# adc_signal.net
KiCad netlist of a schematic drawn in Altium Designer
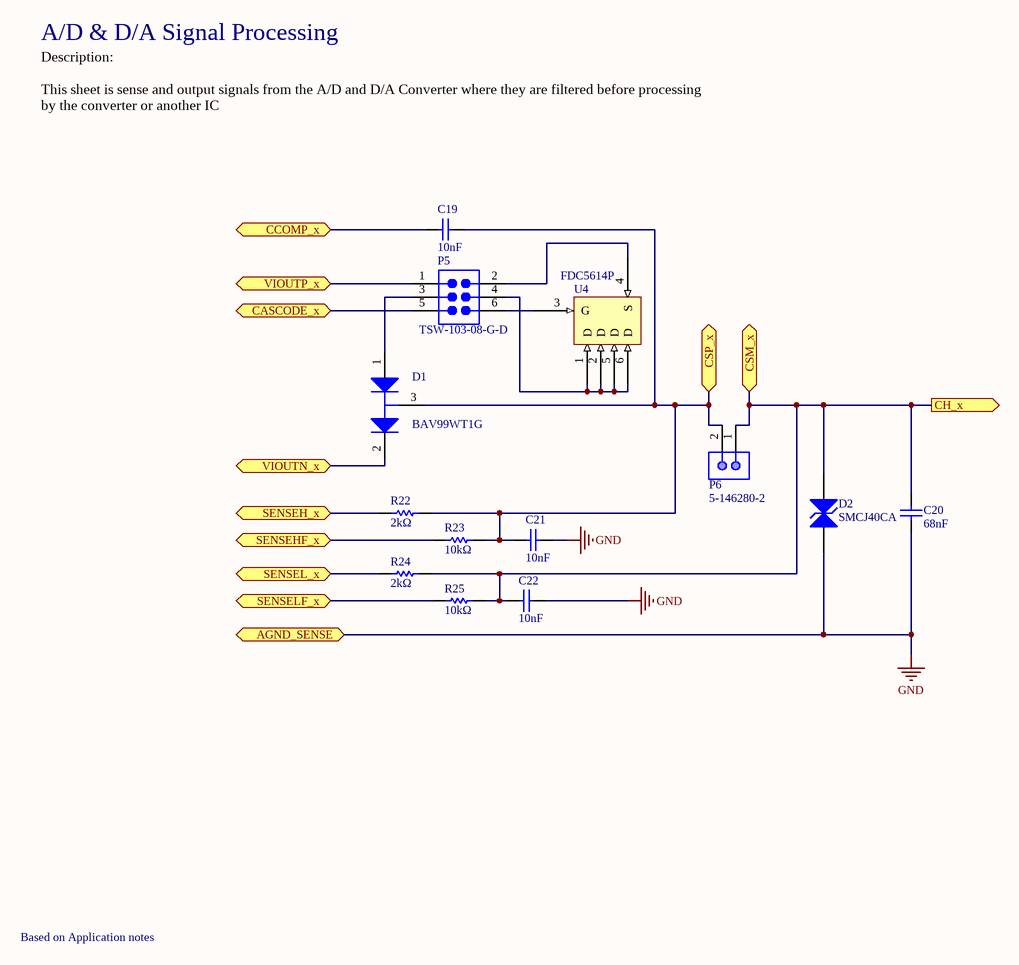
[diagram p0: adc_signal.SchDoc]

(export (version "E")
  (design (tool "Eeschema 10.0.6"))
  (components
    (comp (ref "C19")
      (value "10nF")
      (footprint "CAPC1608X90X35ML10T15")
      (fields
        (field (name "VOLTAGE") "50V")
        (field (name "TOLERANCE") "10%")
        (field (name "MANUFACTURER") "Murata")
      )
      (libsource (lib "Altium Content Vault") (part "CAP-NP-2"))
    )
    (comp (ref "C20")
      (value "68nF")
      (footprint "CAPC1608X90X35LL10T15")
      (description "GRM188R71H683KA93D")
      (fields (field (name "MANUFACTURER") "Murata"))
      (libsource (lib "Altium Content Vault") (part "CAP"))
    )
    (comp (ref "C21")
      (value "10nF")
      (footprint "CAPC1608X90X35ML10T15")
      (fields
        (field (name "VOLTAGE") "50V")
        (field (name "TOLERANCE") "10%")
        (field (name "MANUFACTURER") "Murata")
      )
      (libsource (lib "Altium Content Vault") (part "CAP-NP-2"))
    )
    (comp (ref "C22")
      (value "10nF")
      (footprint "CAPC1608X90X35ML10T15")
      (fields
        (field (name "VOLTAGE") "50V")
        (field (name "TOLERANCE") "10%")
        (field (name "MANUFACTURER") "Murata")
      )
      (libsource (lib "Altium Content Vault") (part "CAP-NP-2"))
    )
    (comp (ref "D1")
      (value "BAV99WT1G")
      (footprint "ONSC-SOT-323-3-419-04_V")
      (description "Dual Series Switching Diodes, 3-Pin SOT-323, Pb-Free, Tape and Reel")
      (fields (field (name "MANUFACTURER") "On Semiconductor"))
      (libsource (lib "Altium Content Vault") (part "ONSC-D-A1K2C3-3"))
    )
    (comp (ref "D2")
      (value "SMCJ40CA")
      (footprint "FAIR-DO-214AB-A-2_V")
      (description "Transient Voltage Suppressor, 1500 W, 40 V, 2-Pin SMD, RoHS, Tape and Reel")
      (fields (field (name "MANUFACTURER") "Fairchild Semiconductor"))
      (libsource (lib "Altium Content Vault") (part "DZEN-AA-2"))
    )
    (comp (ref "P5")
      (value "TSW-103-08-G-D")
      (footprint "SMTC-TSW-103-08-X-D")
      (description "0.025\" SQ Post Header, Through-hole, Vertical, -55 to 125 degC, 2.54 mm Pitch, 6-Pin, Male, RoHS")
      (fields (field (name "MANUFACTURER") "Samtec"))
      (libsource (lib "Altium Content Vault") (part "SMTC-TSW-103-08-X-D"))
    )
    (comp (ref "P6")
      (value "5-146280-2")
      (footprint "TECO-5-146280-2_V")
      (fields (field (name "MANUFACTURER") "TE Connectivity"))
      (libsource (lib "Altium Content Vault") (part "CN-1P-M-R2"))
    )
    (comp (ref "R22")
      (value "2kΩ")
      (footprint "RESC1608X55X30NL20T20")
      (description "ERA3AEB202V")
      (fields (field (name "MANUFACTURER") "Panasonic"))
      (libsource (lib "Altium Content Vault") (part "RES"))
    )
    (comp (ref "R23")
      (value "10kΩ")
      (footprint "RESC1608X55X25ML10T15")
      (fields (field (name "MANUFACTURER") "Yageo") (field (name "TOLERANCE") "1%"))
      (libsource (lib "Altium Content Vault") (part "RES-2"))
    )
    (comp (ref "R24")
      (value "2kΩ")
      (footprint "RESC1608X55X30NL20T20")
      (description "ERA3AEB202V")
      (fields (field (name "MANUFACTURER") "Panasonic"))
      (libsource (lib "Altium Content Vault") (part "RES"))
    )
    (comp (ref "R25")
      (value "10kΩ")
      (footprint "RESC1608X55X25ML10T15")
      (fields (field (name "MANUFACTURER") "Yageo") (field (name "TOLERANCE") "1%"))
      (libsource (lib "Altium Content Vault") (part "RES-2"))
    )
    (comp (ref "U4")
      (value "FDC5614P")
      (footprint "ONSC-CPH-6_V")
      (description "MOSFET P-CH 60V 3A SSOT-6")
      (fields (field (name "VOLTAGE") "60V"))
      (libsource (lib "digital_power") (part "FDC5614P"))
    )
  )
  (nets
    (net (code "1") (name "/CASCODE_x") (class "Default")
      (node (ref "P5") (pin "5") (pinfunction "5_5") (pintype "passive"))
    )
    (net (code "2") (name "/CCOMP_x") (class "Default")
      (node (ref "C19") (pin "1") (pinfunction "1_1") (pintype "passive"))
    )
    (net (code "3") (name "/CH_x") (class "Default")
      (node (ref "C20") (pin "2") (pinfunction "2_2") (pintype "passive"))
      (node (ref "C22") (pin "2") (pinfunction "2_2") (pintype "passive"))
      (node (ref "D2") (pin "2") (pinfunction "A_2") (pintype "passive"))
      (node (ref "P6") (pin "1") (pinfunction "1_1") (pintype "passive"))
      (node (ref "R24") (pin "2") (pinfunction "2_2") (pintype "passive"))
      (node (ref "R25") (pin "2") (pinfunction "2_2") (pintype "passive"))
    )
    (net (code "4") (name "/CSP_x") (class "Default")
      (node (ref "C19") (pin "2") (pinfunction "2_2") (pintype "passive"))
      (node (ref "C21") (pin "2") (pinfunction "2_2") (pintype "passive"))
      (node (ref "D1") (pin "3") (pinfunction "K/A_3") (pintype "passive"))
      (node (ref "P6") (pin "2") (pinfunction "2_2") (pintype "passive"))
      (node (ref "R22") (pin "2") (pinfunction "2_2") (pintype "passive"))
      (node (ref "R23") (pin "2") (pinfunction "2_2") (pintype "passive"))
    )
    (net (code "5") (name "/SENSEHF_x") (class "Default")
      (node (ref "R23") (pin "1") (pinfunction "1_1") (pintype "passive"))
    )
    (net (code "6") (name "/SENSEH_x") (class "Default")
      (node (ref "R22") (pin "1") (pinfunction "1_1") (pintype "passive"))
    )
    (net (code "7") (name "/SENSELF_x") (class "Default")
      (node (ref "R25") (pin "1") (pinfunction "1_1") (pintype "passive"))
    )
    (net (code "8") (name "/SENSEL_x") (class "Default")
      (node (ref "R24") (pin "1") (pinfunction "1_1") (pintype "passive"))
    )
    (net (code "9") (name "/VIOUTN_x") (class "Default")
      (node (ref "D1") (pin "2") (pinfunction "K_2") (pintype "passive"))
    )
    (net (code "10") (name "/VIOUTP_x") (class "Default")
      (node (ref "P5") (pin "1") (pinfunction "1_1") (pintype "passive"))
    )
    (net (code "11") (name "GND") (class "Default")
      (node (ref "C20") (pin "1") (pinfunction "1_1") (pintype "passive"))
      (node (ref "C21") (pin "1") (pinfunction "1_1") (pintype "passive"))
      (node (ref "C22") (pin "1") (pinfunction "1_1") (pintype "passive"))
      (node (ref "D2") (pin "1") (pinfunction "A_1") (pintype "passive"))
    )
    (net (code "12") (name "Net-(D1-A)") (class "Default")
      (node (ref "D1") (pin "1") (pinfunction "A_1") (pintype "passive"))
      (node (ref "P5") (pin "3") (pinfunction "3_3") (pintype "passive"))
    )
    (net (code "13") (name "Net-(P5-Pad4)") (class "Default")
      (node (ref "P5") (pin "4") (pinfunction "4_4") (pintype "passive"))
      (node (ref "U4") (pin "1") (pinfunction "D_1") (pintype "input"))
      (node (ref "U4") (pin "2") (pinfunction "D_2") (pintype "input"))
      (node (ref "U4") (pin "5") (pinfunction "D_5") (pintype "input"))
      (node (ref "U4") (pin "6") (pinfunction "D_6") (pintype "input"))
    )
    (net (code "14") (name "Net-(U4-G)") (class "Default")
      (node (ref "P5") (pin "6") (pinfunction "6_6") (pintype "passive"))
      (node (ref "U4") (pin "3") (pinfunction "G_3") (pintype "input"))
    )
    (net (code "15") (name "Net-(U4-S)") (class "Default")
      (node (ref "P5") (pin "2") (pinfunction "2_2") (pintype "passive"))
      (node (ref "U4") (pin "4") (pinfunction "S_4") (pintype "input"))
    )
  )
)
